# WiFi_TF_EMMC.net
KiCad netlist of a schematic drawn in Altium Designer
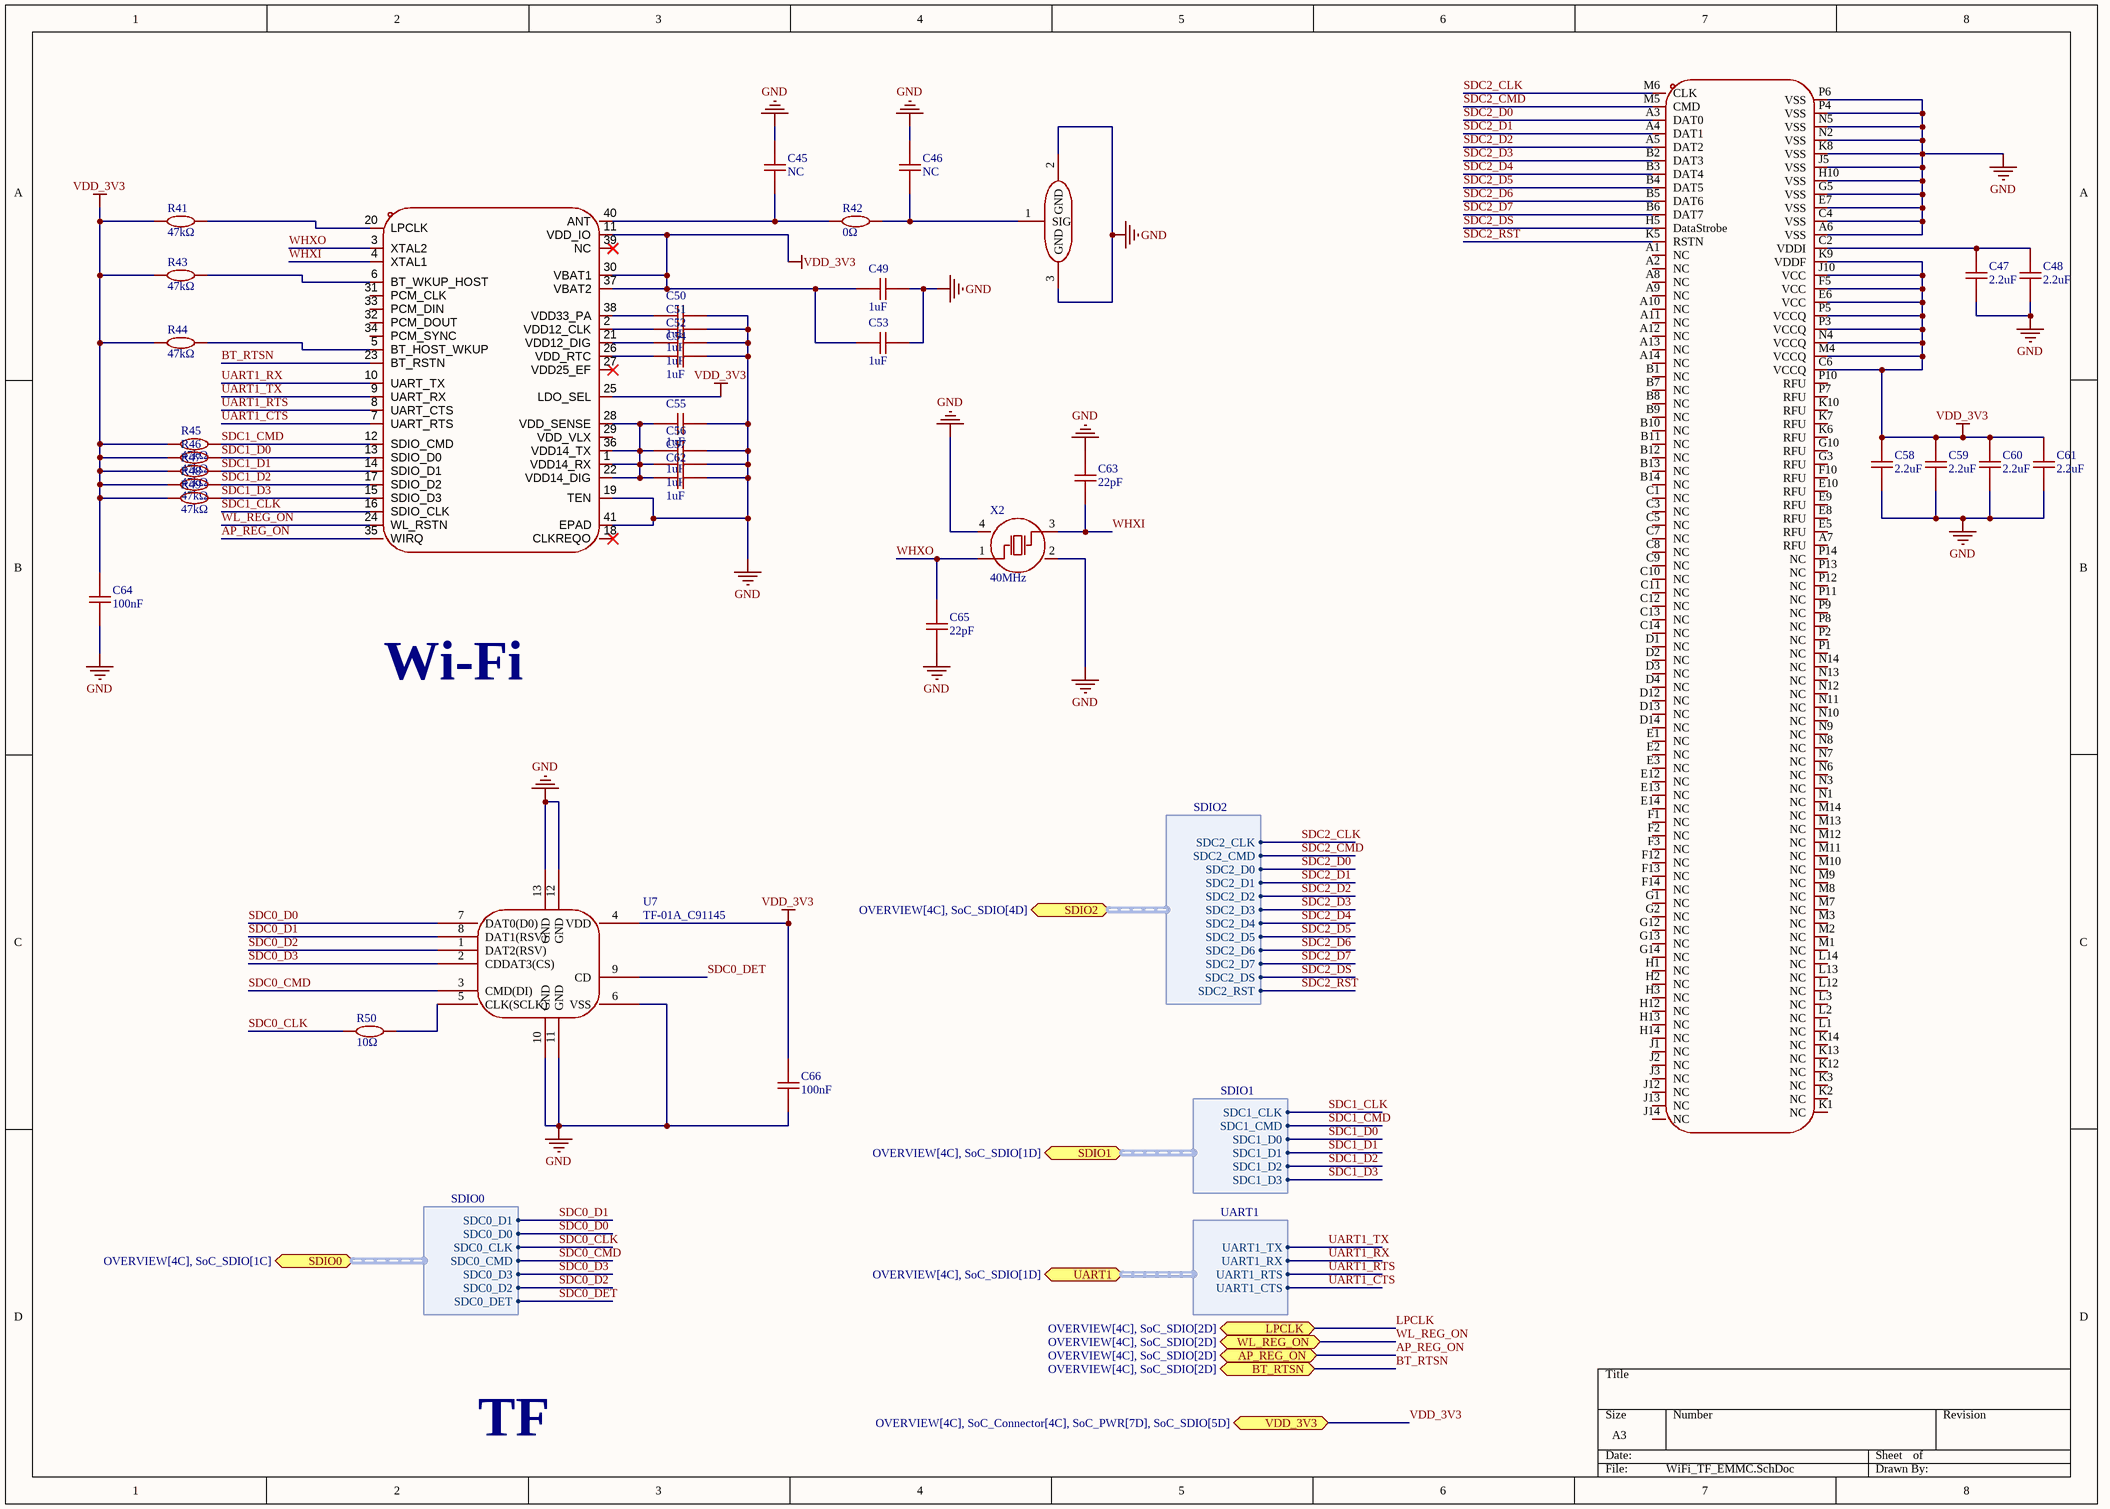
[diagram p0: WiFi_TF_EMMC.SchDoc]

(export (version "E")
  (design (tool "Eeschema 10.0.6"))
  (components
    (comp (ref "C45")
      (value "NC")
      (footprint "C0402")
      (description "50V 100nF X7R ±10% 0402 Ceramic Capacitors ROHS")
      (libsource (lib "RLC") (part "100nF"))
    )
    (comp (ref "C46")
      (value "NC")
      (footprint "C0402")
      (description "50V 100nF X7R ±10% 0402 Ceramic Capacitors ROHS")
      (libsource (lib "RLC") (part "100nF"))
    )
    (comp (ref "C47")
      (value "2.2uF")
      (footprint "C0402")
      (description "50V 2.2uF NP0 0402 Ceramic Capacitors ROHS")
      (libsource (lib "RLC") (part "2.2uF"))
    )
    (comp (ref "C48")
      (value "2.2uF")
      (footprint "C0402")
      (description "50V 2.2uF NP0 0402 Ceramic Capacitors ROHS")
      (libsource (lib "RLC") (part "2.2uF"))
    )
    (comp (ref "C49")
      (value "1uF")
      (footprint "C0402")
      (description "50V 1uF X5R ±10% 0402 Ceramic Capacitors ROHS")
      (libsource (lib "RLC") (part "1uF"))
    )
    (comp (ref "C50")
      (value "1uF")
      (footprint "C0402")
      (description "50V 1uF X5R ±10% 0402 Ceramic Capacitors ROHS")
      (libsource (lib "RLC") (part "1uF"))
    )
    (comp (ref "C51")
      (value "1uF")
      (footprint "C0402")
      (description "50V 1uF X5R ±10% 0402 Ceramic Capacitors ROHS")
      (libsource (lib "RLC") (part "1uF"))
    )
    (comp (ref "C52")
      (value "1uF")
      (footprint "C0402")
      (description "50V 1uF X5R ±10% 0402 Ceramic Capacitors ROHS")
      (libsource (lib "RLC") (part "1uF"))
    )
    (comp (ref "C53")
      (value "1uF")
      (footprint "C0402")
      (description "50V 1uF X5R ±10% 0402 Ceramic Capacitors ROHS")
      (libsource (lib "RLC") (part "1uF"))
    )
    (comp (ref "C54")
      (value "1uF")
      (footprint "C0402")
      (description "50V 1uF X5R ±10% 0402 Ceramic Capacitors ROHS")
      (libsource (lib "RLC") (part "1uF"))
    )
    (comp (ref "C55")
      (value "1uF")
      (footprint "C0402")
      (description "50V 1uF X5R ±10% 0402 Ceramic Capacitors ROHS")
      (libsource (lib "RLC") (part "1uF"))
    )
    (comp (ref "C56")
      (value "1uF")
      (footprint "C0402")
      (description "50V 1uF X5R ±10% 0402 Ceramic Capacitors ROHS")
      (libsource (lib "RLC") (part "1uF"))
    )
    (comp (ref "C57")
      (value "1uF")
      (footprint "C0402")
      (description "50V 1uF X5R ±10% 0402 Ceramic Capacitors ROHS")
      (libsource (lib "RLC") (part "1uF"))
    )
    (comp (ref "C58")
      (value "2.2uF")
      (footprint "C0402")
      (description "50V 2.2uF NP0 0402 Ceramic Capacitors ROHS")
      (libsource (lib "RLC") (part "2.2uF"))
    )
    (comp (ref "C59")
      (value "2.2uF")
      (footprint "C0402")
      (description "50V 2.2uF NP0 0402 Ceramic Capacitors ROHS")
      (libsource (lib "RLC") (part "2.2uF"))
    )
    (comp (ref "C60")
      (value "2.2uF")
      (footprint "C0402")
      (description "50V 2.2uF NP0 0402 Ceramic Capacitors ROHS")
      (libsource (lib "RLC") (part "2.2uF"))
    )
    (comp (ref "C61")
      (value "2.2uF")
      (footprint "C0402")
      (description "50V 2.2uF NP0 0402 Ceramic Capacitors ROHS")
      (libsource (lib "RLC") (part "2.2uF"))
    )
    (comp (ref "C62")
      (value "1uF")
      (footprint "C0402")
      (description "50V 1uF X5R ±10% 0402 Ceramic Capacitors ROHS")
      (libsource (lib "RLC") (part "1uF"))
    )
    (comp (ref "C63")
      (value "22pF")
      (footprint "C0402")
      (description "50V 22pF C0G ±5% 0402 Ceramic Capacitors ROHS")
      (libsource (lib "RLC") (part "22pF"))
    )
    (comp (ref "C64")
      (value "100nF")
      (footprint "C0402")
      (description "50V 100nF X7R ±10% 0402 Ceramic Capacitors ROHS")
      (libsource (lib "RLC") (part "100nF"))
    )
    (comp (ref "C65")
      (value "22pF")
      (footprint "C0402")
      (description "50V 22pF C0G ±5% 0402 Ceramic Capacitors ROHS")
      (libsource (lib "RLC") (part "22pF"))
    )
    (comp (ref "C66")
      (value "100nF")
      (footprint "C0402")
      (description "50V 100nF X7R ±10% 0402 Ceramic Capacitors ROHS")
      (libsource (lib "RLC") (part "100nF"))
    )
    (comp (ref "JP1")
      (value "6GHz")
      (footprint "RF-SMD_FRF05002-JSS103M")
      (fields (field (name "MANUFACTURER") "HRS(广濑)") (field (name "MANUFACTURER PART") "U.FL-R-SMT-1(80)"))
      (libsource (lib "Connector") (part "U.FL-R-SMT-1(80)_C88374"))
    )
    (comp (ref "R41")
      (value "47kΩ")
      (footprint "R0402")
      (description "62.5mW 47kΩ 50V ±100ppm/℃ Thick Film Resistor ±1% 0402 Chip Resistor - Surface Mount ROHS")
      (libsource (lib "RLC") (part "47kΩ"))
    )
    (comp (ref "R42")
      (value "0Ω")
      (footprint "R0402")
      (description "0Ω 62.5mW 50V Thick Film Resistor ±1% 0402 Chip Resistor - Surface Mount ROHS")
      (libsource (lib "RLC") (part "0Ω"))
    )
    (comp (ref "R43")
      (value "47kΩ")
      (footprint "R0402")
      (description "62.5mW 47kΩ 50V ±100ppm/℃ Thick Film Resistor ±1% 0402 Chip Resistor - Surface Mount ROHS")
      (libsource (lib "RLC") (part "47kΩ"))
    )
    (comp (ref "R44")
      (value "47kΩ")
      (footprint "R0402")
      (description "62.5mW 47kΩ 50V ±100ppm/℃ Thick Film Resistor ±1% 0402 Chip Resistor - Surface Mount ROHS")
      (libsource (lib "RLC") (part "47kΩ"))
    )
    (comp (ref "R45")
      (value "47kΩ")
      (footprint "R0402")
      (description "62.5mW 47kΩ 50V ±100ppm/℃ Thick Film Resistor ±1% 0402 Chip Resistor - Surface Mount ROHS")
      (libsource (lib "RLC") (part "47kΩ"))
    )
    (comp (ref "R46")
      (value "47kΩ")
      (footprint "R0402")
      (description "62.5mW 47kΩ 50V ±100ppm/℃ Thick Film Resistor ±1% 0402 Chip Resistor - Surface Mount ROHS")
      (libsource (lib "RLC") (part "47kΩ"))
    )
    (comp (ref "R47")
      (value "47kΩ")
      (footprint "R0402")
      (description "62.5mW 47kΩ 50V ±100ppm/℃ Thick Film Resistor ±1% 0402 Chip Resistor - Surface Mount ROHS")
      (libsource (lib "RLC") (part "47kΩ"))
    )
    (comp (ref "R48")
      (value "47kΩ")
      (footprint "R0402")
      (description "62.5mW 47kΩ 50V ±100ppm/℃ Thick Film Resistor ±1% 0402 Chip Resistor - Surface Mount ROHS")
      (libsource (lib "RLC") (part "47kΩ"))
    )
    (comp (ref "R49")
      (value "47kΩ")
      (footprint "R0402")
      (description "62.5mW 47kΩ 50V ±100ppm/℃ Thick Film Resistor ±1% 0402 Chip Resistor - Surface Mount ROHS")
      (libsource (lib "RLC") (part "47kΩ"))
    )
    (comp (ref "R50")
      (value "10Ω")
      (footprint "R0402")
      (description "10Ω 62.5mW 50V ±200ppm/℃ Thick Film Resistor ±1% 0402 Chip Resistor - Surface Mount ROHS")
      (libsource (lib "RLC") (part "10Ω"))
    )
    (comp (ref "U6")
      (value "XR829")
      (footprint "QFN-40_L5.0-W5.0-P0.40-BL-EP3.4")
      (description "2.4GHz WiFi and Bluetooth chips")
      (libsource (lib "IC") (part "XR829"))
    )
    (comp (ref "U7")
      (value "TF-01A_C91145")
      (footprint "TF-SMD_TF-01A")
      (description "Push-Push 1.85mm Connector and Ejector MicroSD Card (TF Card) SMD PC Card Sockets ROHS")
      (libsource (lib "IC") (part "TF-01A_C91145"))
    )
    (comp (ref "U8")
      (value "KLM8G1GETF-B041")
      (footprint "FBGA-153_L13.0-W11.5-P0.50_KLMAG1JETD-B041")
      (description "8GB 2.7V~3.6V eMMC 5.1 330/50 MB/s FBGA-153(11.5x13) Memory (ICs) ROHS")
      (fields (field (name "MANUFACTURER") "SAMSUNG(三星半导体)"))
      (libsource (lib "IC") (part "KLM8G1GETF-B041_1"))
    )
    (comp (ref "X2")
      (value "40MHz")
      (footprint "OSC-SMD_4P-L3.2-W2.5-BL_SIT8008BI")
      (description "Crystal Oscillator 15pF SMD3225-4P Crystals ROHS")
      (libsource (lib "OSC") (part "X322540MPB4SI"))
    )
  )
  (nets
    (net (code "5") (name "/AP_REG_ON") (class "Default")
      (node (ref "U6") (pin "35") (pinfunction "WIRQ_35") (pintype "passive"))
    )
    (net (code "6") (name "/BT_RTSN") (class "Default")
      (node (ref "U6") (pin "23") (pinfunction "BT_RSTN_23") (pintype "passive"))
    )
    (net (code "8") (name "/SDC0_CLK") (class "Default")
      (node (ref "R50") (pin "1") (pinfunction "1_1") (pintype "passive"))
    )
    (net (code "9") (name "/SDC0_CMD") (class "Default")
      (node (ref "U7") (pin "3") (pinfunction "CMD(DI)_3") (pintype "passive"))
    )
    (net (code "10") (name "/SDC0_D0") (class "Default")
      (node (ref "U7") (pin "7") (pinfunction "DAT0(D0)_7") (pintype "passive"))
    )
    (net (code "11") (name "/SDC0_D1") (class "Default")
      (node (ref "U7") (pin "8") (pinfunction "DAT1(RSV)_8") (pintype "passive"))
    )
    (net (code "12") (name "/SDC0_D2") (class "Default")
      (node (ref "U7") (pin "1") (pinfunction "DAT2(RSV)_1") (pintype "passive"))
    )
    (net (code "13") (name "/SDC0_D3") (class "Default")
      (node (ref "U7") (pin "2") (pinfunction "CDDAT3(CS)_2") (pintype "passive"))
    )
    (net (code "14") (name "/SDC0_DET") (class "Default")
      (node (ref "U7") (pin "9") (pinfunction "CD_9") (pintype "passive"))
    )
    (net (code "15") (name "/SDC1_CLK") (class "Default")
      (node (ref "U6") (pin "16") (pinfunction "SDIO_CLK_16") (pintype "passive"))
    )
    (net (code "16") (name "/SDC1_CMD") (class "Default")
      (node (ref "R45") (pin "2") (pinfunction "2_2") (pintype "passive"))
      (node (ref "U6") (pin "12") (pinfunction "SDIO_CMD_12") (pintype "passive"))
    )
    (net (code "17") (name "/SDC1_D0") (class "Default")
      (node (ref "R46") (pin "2") (pinfunction "2_2") (pintype "passive"))
      (node (ref "U6") (pin "13") (pinfunction "SDIO_D0_13") (pintype "passive"))
    )
    (net (code "18") (name "/SDC1_D1") (class "Default")
      (node (ref "R47") (pin "2") (pinfunction "2_2") (pintype "passive"))
      (node (ref "U6") (pin "14") (pinfunction "SDIO_D1_14") (pintype "passive"))
    )
    (net (code "19") (name "/SDC1_D2") (class "Default")
      (node (ref "R48") (pin "2") (pinfunction "2_2") (pintype "passive"))
      (node (ref "U6") (pin "17") (pinfunction "SDIO_D2_17") (pintype "passive"))
    )
    (net (code "20") (name "/SDC1_D3") (class "Default")
      (node (ref "R49") (pin "2") (pinfunction "2_2") (pintype "passive"))
      (node (ref "U6") (pin "15") (pinfunction "SDIO_D3_15") (pintype "passive"))
    )
    (net (code "21") (name "/SDC2_CLK") (class "Default")
      (node (ref "U8") (pin "M6") (pinfunction "CLK_M6") (pintype "passive"))
    )
    (net (code "22") (name "/SDC2_CMD") (class "Default")
      (node (ref "U8") (pin "M5") (pinfunction "CMD_M5") (pintype "passive"))
    )
    (net (code "23") (name "/SDC2_D0") (class "Default")
      (node (ref "U8") (pin "A3") (pinfunction "DAT0_A3") (pintype "passive"))
    )
    (net (code "24") (name "/SDC2_D1") (class "Default")
      (node (ref "U8") (pin "A4") (pinfunction "DAT1_A4") (pintype "passive"))
    )
    (net (code "25") (name "/SDC2_D2") (class "Default")
      (node (ref "U8") (pin "A5") (pinfunction "DAT2_A5") (pintype "passive"))
    )
    (net (code "26") (name "/SDC2_D3") (class "Default")
      (node (ref "U8") (pin "B2") (pinfunction "DAT3_B2") (pintype "passive"))
    )
    (net (code "27") (name "/SDC2_D4") (class "Default")
      (node (ref "U8") (pin "B3") (pinfunction "DAT4_B3") (pintype "passive"))
    )
    (net (code "28") (name "/SDC2_D5") (class "Default")
      (node (ref "U8") (pin "B4") (pinfunction "DAT5_B4") (pintype "passive"))
    )
    (net (code "29") (name "/SDC2_D6") (class "Default")
      (node (ref "U8") (pin "B5") (pinfunction "DAT6_B5") (pintype "passive"))
    )
    (net (code "30") (name "/SDC2_D7") (class "Default")
      (node (ref "U8") (pin "B6") (pinfunction "DAT7_B6") (pintype "passive"))
    )
    (net (code "31") (name "/SDC2_DS") (class "Default")
      (node (ref "U8") (pin "H5") (pinfunction "DataStrobe_H5") (pintype "passive"))
    )
    (net (code "32") (name "/SDC2_RST") (class "Default")
      (node (ref "U8") (pin "K5") (pinfunction "RSTN_K5") (pintype "passive"))
    )
    (net (code "33") (name "/UART1_CTS") (class "Default")
      (node (ref "U6") (pin "7") (pinfunction "UART_RTS_7") (pintype "passive"))
    )
    (net (code "34") (name "/UART1_RTS") (class "Default")
      (node (ref "U6") (pin "8") (pinfunction "UART_CTS_8") (pintype "passive"))
    )
    (net (code "35") (name "/UART1_RX") (class "Default")
      (node (ref "U6") (pin "10") (pinfunction "UART_TX_10") (pintype "passive"))
    )
    (net (code "36") (name "/UART1_TX") (class "Default")
      (node (ref "U6") (pin "9") (pinfunction "UART_RX_9") (pintype "passive"))
    )
    (net (code "37") (name "/WHXI") (class "Default")
      (node (ref "C63") (pin "1") (pinfunction "1_1") (pintype "passive"))
      (node (ref "U6") (pin "4") (pinfunction "XTAL1_4") (pintype "passive"))
      (node (ref "X2") (pin "3") (pinfunction "OSC2_3") (pintype "passive"))
    )
    (net (code "38") (name "/WHXO") (class "Default")
      (node (ref "C65") (pin "2") (pinfunction "2_2") (pintype "passive"))
      (node (ref "U6") (pin "3") (pinfunction "XTAL2_3") (pintype "passive"))
      (node (ref "X2") (pin "1") (pinfunction "OSC1_1") (pintype "passive"))
    )
    (net (code "39") (name "/WL_REG_ON") (class "Default")
      (node (ref "U6") (pin "24") (pinfunction "WL_RSTN_24") (pintype "passive"))
    )
    (net (code "44") (name "GND") (class "Default")
      (node (ref "C45") (pin "2") (pinfunction "2_2") (pintype "passive"))
      (node (ref "C46") (pin "2") (pinfunction "2_2") (pintype "passive"))
      (node (ref "C47") (pin "1") (pinfunction "1_1") (pintype "passive"))
      (node (ref "C48") (pin "1") (pinfunction "1_1") (pintype "passive"))
      (node (ref "C49") (pin "1") (pinfunction "1_1") (pintype "passive"))
      (node (ref "C50") (pin "1") (pinfunction "1_1") (pintype "passive"))
      (node (ref "C51") (pin "1") (pinfunction "1_1") (pintype "passive"))
      (node (ref "C52") (pin "1") (pinfunction "1_1") (pintype "passive"))
      (node (ref "C53") (pin "1") (pinfunction "1_1") (pintype "passive"))
      (node (ref "C54") (pin "1") (pinfunction "1_1") (pintype "passive"))
      (node (ref "C55") (pin "1") (pinfunction "1_1") (pintype "passive"))
      (node (ref "C56") (pin "1") (pinfunction "1_1") (pintype "passive"))
      (node (ref "C57") (pin "1") (pinfunction "1_1") (pintype "passive"))
      (node (ref "C58") (pin "1") (pinfunction "1_1") (pintype "passive"))
      (node (ref "C59") (pin "1") (pinfunction "1_1") (pintype "passive"))
      (node (ref "C60") (pin "1") (pinfunction "1_1") (pintype "passive"))
      (node (ref "C61") (pin "1") (pinfunction "1_1") (pintype "passive"))
      (node (ref "C62") (pin "1") (pinfunction "1_1") (pintype "passive"))
      (node (ref "C63") (pin "2") (pinfunction "2_2") (pintype "passive"))
      (node (ref "C64") (pin "1") (pinfunction "1_1") (pintype "passive"))
      (node (ref "C65") (pin "1") (pinfunction "1_1") (pintype "passive"))
      (node (ref "C66") (pin "1") (pinfunction "1_1") (pintype "passive"))
      (node (ref "JP1") (pin "2") (pinfunction "GND_2") (pintype "passive"))
      (node (ref "JP1") (pin "3") (pinfunction "GND_3") (pintype "passive"))
      (node (ref "U6") (pin "19") (pinfunction "TEN_19") (pintype "passive"))
      (node (ref "U6") (pin "41") (pinfunction "EPAD_41") (pintype "passive"))
      (node (ref "U7") (pin "10") (pinfunction "GND_10") (pintype "passive"))
      (node (ref "U7") (pin "11") (pinfunction "GND_11") (pintype "passive"))
      (node (ref "U7") (pin "12") (pinfunction "GND_12") (pintype "passive"))
      (node (ref "U7") (pin "13") (pinfunction "GND_13") (pintype "passive"))
      (node (ref "U7") (pin "6") (pinfunction "VSS_6") (pintype "passive"))
      (node (ref "U8") (pin "A6") (pinfunction "VSS_A6") (pintype "passive"))
      (node (ref "U8") (pin "C4") (pinfunction "VSS_C4") (pintype "passive"))
      (node (ref "U8") (pin "E7") (pinfunction "VSS_E7") (pintype "passive"))
      (node (ref "U8") (pin "G5") (pinfunction "VSS_G5") (pintype "passive"))
      (node (ref "U8") (pin "H10") (pinfunction "VSS_H10") (pintype "passive"))
      (node (ref "U8") (pin "J5") (pinfunction "VSS_J5") (pintype "passive"))
      (node (ref "U8") (pin "K8") (pinfunction "VSS_K8") (pintype "passive"))
      (node (ref "U8") (pin "N2") (pinfunction "VSS_N2") (pintype "passive"))
      (node (ref "U8") (pin "N5") (pinfunction "VSS_N5") (pintype "passive"))
      (node (ref "U8") (pin "P4") (pinfunction "VSS_P4") (pintype "passive"))
      (node (ref "U8") (pin "P6") (pinfunction "VSS_P6") (pintype "passive"))
      (node (ref "X2") (pin "2") (pinfunction "GND_2") (pintype "passive"))
      (node (ref "X2") (pin "4") (pinfunction "GND_4") (pintype "passive"))
    )
    (net (code "45") (name "Net-(JP1-SIG)") (class "Default")
      (node (ref "C46") (pin "1") (pinfunction "1_1") (pintype "passive"))
      (node (ref "JP1") (pin "1") (pinfunction "SIG_1") (pintype "passive"))
      (node (ref "R42") (pin "2") (pinfunction "2_2") (pintype "passive"))
    )
    (net (code "46") (name "Net-(U6-ANT)") (class "Default")
      (node (ref "C45") (pin "1") (pinfunction "1_1") (pintype "passive"))
      (node (ref "R42") (pin "1") (pinfunction "1_1") (pintype "passive"))
      (node (ref "U6") (pin "40") (pinfunction "ANT_40") (pintype "passive"))
    )
    (net (code "47") (name "Net-(U6-BT_HOST_WKUP)") (class "Default")
      (node (ref "R44") (pin "2") (pinfunction "2_2") (pintype "passive"))
      (node (ref "U6") (pin "5") (pinfunction "BT_HOST_WKUP_5") (pintype "passive"))
    )
    (net (code "48") (name "Net-(U6-BT_WKUP_HOST)") (class "Default")
      (node (ref "R43") (pin "2") (pinfunction "2_2") (pintype "passive"))
      (node (ref "U6") (pin "6") (pinfunction "BT_WKUP_HOST_6") (pintype "passive"))
    )
    (net (code "49") (name "Net-(U6-LPCLK)") (class "Default")
      (node (ref "R41") (pin "2") (pinfunction "2_2") (pintype "passive"))
      (node (ref "U6") (pin "20") (pinfunction "LPCLK_20") (pintype "passive"))
    )
    (net (code "50") (name "Net-(U6-VDD12_CLK)") (class "Default")
      (node (ref "C51") (pin "2") (pinfunction "2_2") (pintype "passive"))
      (node (ref "U6") (pin "2") (pinfunction "VDD12_CLK_2") (pintype "passive"))
    )
    (net (code "51") (name "Net-(U6-VDD12_DIG)") (class "Default")
      (node (ref "C52") (pin "2") (pinfunction "2_2") (pintype "passive"))
      (node (ref "U6") (pin "21") (pinfunction "VDD12_DIG_21") (pintype "passive"))
    )
    (net (code "52") (name "Net-(U6-VDD14_DIG)") (class "Default")
      (node (ref "C55") (pin "2") (pinfunction "2_2") (pintype "passive"))
      (node (ref "C56") (pin "2") (pinfunction "2_2") (pintype "passive"))
      (node (ref "C57") (pin "2") (pinfunction "2_2") (pintype "passive"))
      (node (ref "C62") (pin "2") (pinfunction "2_2") (pintype "passive"))
      (node (ref "U6") (pin "1") (pinfunction "VDD14_RX_1") (pintype "passive"))
      (node (ref "U6") (pin "22") (pinfunction "VDD14_DIG_22") (pintype "passive"))
      (node (ref "U6") (pin "28") (pinfunction "VDD_SENSE_28") (pintype "passive"))
      (node (ref "U6") (pin "36") (pinfunction "VDD14_TX_36") (pintype "passive"))
    )
    (net (code "53") (name "Net-(U6-VDD33_PA)") (class "Default")
      (node (ref "C50") (pin "2") (pinfunction "2_2") (pintype "passive"))
      (node (ref "U6") (pin "38") (pinfunction "VDD33_PA_38") (pintype "passive"))
    )
    (net (code "54") (name "Net-(U6-VDD_RTC)") (class "Default")
      (node (ref "C54") (pin "2") (pinfunction "2_2") (pintype "passive"))
      (node (ref "U6") (pin "26") (pinfunction "VDD_RTC_26") (pintype "passive"))
    )
    (net (code "55") (name "Net-(U7-CLK(SCLK))") (class "Default")
      (node (ref "R50") (pin "2") (pinfunction "2_2") (pintype "passive"))
      (node (ref "U7") (pin "5") (pinfunction "CLK(SCLK)_5") (pintype "passive"))
    )
    (net (code "56") (name "Net-(U8-VDDI)") (class "Default")
      (node (ref "C47") (pin "2") (pinfunction "2_2") (pintype "passive"))
      (node (ref "C48") (pin "2") (pinfunction "2_2") (pintype "passive"))
      (node (ref "U8") (pin "C2") (pinfunction "VDDI_C2") (pintype "passive"))
    )
    (net (code "57") (name "VDD_3V3") (class "Default")
      (node (ref "C49") (pin "2") (pinfunction "2_2") (pintype "passive"))
      (node (ref "C53") (pin "2") (pinfunction "2_2") (pintype "passive"))
      (node (ref "C58") (pin "2") (pinfunction "2_2") (pintype "passive"))
      (node (ref "C59") (pin "2") (pinfunction "2_2") (pintype "passive"))
      (node (ref "C60") (pin "2") (pinfunction "2_2") (pintype "passive"))
      (node (ref "C61") (pin "2") (pinfunction "2_2") (pintype "passive"))
      (node (ref "C64") (pin "2") (pinfunction "2_2") (pintype "passive"))
      (node (ref "C66") (pin "2") (pinfunction "2_2") (pintype "passive"))
      (node (ref "R41") (pin "1") (pinfunction "1_1") (pintype "passive"))
      (node (ref "R43") (pin "1") (pinfunction "1_1") (pintype "passive"))
      (node (ref "R44") (pin "1") (pinfunction "1_1") (pintype "passive"))
      (node (ref "R45") (pin "1") (pinfunction "1_1") (pintype "passive"))
      (node (ref "R46") (pin "1") (pinfunction "1_1") (pintype "passive"))
      (node (ref "R47") (pin "1") (pinfunction "1_1") (pintype "passive"))
      (node (ref "R48") (pin "1") (pinfunction "1_1") (pintype "passive"))
      (node (ref "R49") (pin "1") (pinfunction "1_1") (pintype "passive"))
      (node (ref "U6") (pin "11") (pinfunction "VDD_IO_11") (pintype "passive"))
      (node (ref "U6") (pin "25") (pinfunction "LDO_SEL_25") (pintype "passive"))
      (node (ref "U6") (pin "30") (pinfunction "VBAT1_30") (pintype "passive"))
      (node (ref "U6") (pin "37") (pinfunction "VBAT2_37") (pintype "passive"))
      (node (ref "U7") (pin "4") (pinfunction "VDD_4") (pintype "passive"))
      (node (ref "U8") (pin "C6") (pinfunction "VCCQ_C6") (pintype "passive"))
      (node (ref "U8") (pin "E6") (pinfunction "VCC_E6") (pintype "passive"))
      (node (ref "U8") (pin "F5") (pinfunction "VCC_F5") (pintype "passive"))
      (node (ref "U8") (pin "J10") (pinfunction "VCC_J10") (pintype "passive"))
      (node (ref "U8") (pin "K9") (pinfunction "VDDF_K9") (pintype "passive"))
      (node (ref "U8") (pin "M4") (pinfunction "VCCQ_M4") (pintype "passive"))
      (node (ref "U8") (pin "N4") (pinfunction "VCCQ_N4") (pintype "passive"))
      (node (ref "U8") (pin "P3") (pinfunction "VCCQ_P3") (pintype "passive"))
      (node (ref "U8") (pin "P5") (pinfunction "VCCQ_P5") (pintype "passive"))
    )
    (net (code "58") (name "unconnected-(U6-CLKREQO-Pad18)") (class "Default")
      (node (ref "U6") (pin "18") (pinfunction "CLKREQO_18") (pintype "passive+no_connect"))
    )
    (net (code "59") (name "unconnected-(U6-NC-Pad39)") (class "Default")
      (node (ref "U6") (pin "39") (pinfunction "NC_39") (pintype "passive+no_connect"))
    )
    (net (code "60") (name "unconnected-(U6-PCM_CLK-Pad31)") (class "Default")
      (node (ref "U6") (pin "31") (pinfunction "PCM_CLK_31") (pintype "passive"))
    )
    (net (code "61") (name "unconnected-(U6-PCM_DIN-Pad33)") (class "Default")
      (node (ref "U6") (pin "33") (pinfunction "PCM_DIN_33") (pintype "passive"))
    )
    (net (code "62") (name "unconnected-(U6-PCM_DOUT-Pad32)") (class "Default")
      (node (ref "U6") (pin "32") (pinfunction "PCM_DOUT_32") (pintype "passive"))
    )
    (net (code "63") (name "unconnected-(U6-PCM_SYNC-Pad34)") (class "Default")
      (node (ref "U6") (pin "34") (pinfunction "PCM_SYNC_34") (pintype "passive"))
    )
    (net (code "64") (name "unconnected-(U6-VDD25_EF-Pad27)") (class "Default")
      (node (ref "U6") (pin "27") (pinfunction "VDD25_EF_27") (pintype "passive+no_connect"))
    )
    (net (code "65") (name "unconnected-(U6-VDD_VLX-Pad29)") (class "Default")
      (node (ref "U6") (pin "29") (pinfunction "VDD_VLX_29") (pintype "passive"))
    )
    (net (code "66") (name "unconnected-(U8-NC-PadA1)") (class "Default")
      (node (ref "U8") (pin "A1") (pinfunction "NC_A1") (pintype "passive"))
    )
    (net (code "67") (name "unconnected-(U8-NC-PadA2)") (class "Default")
      (node (ref "U8") (pin "A2") (pinfunction "NC_A2") (pintype "passive"))
    )
    (net (code "68") (name "unconnected-(U8-NC-PadA8)") (class "Default")
      (node (ref "U8") (pin "A8") (pinfunction "NC_A8") (pintype "passive"))
    )
    (net (code "69") (name "unconnected-(U8-NC-PadA9)") (class "Default")
      (node (ref "U8") (pin "A9") (pinfunction "NC_A9") (pintype "passive"))
    )
    (net (code "70") (name "unconnected-(U8-NC-PadA10)") (class "Default")
      (node (ref "U8") (pin "A10") (pinfunction "NC_A10") (pintype "passive"))
    )
    (net (code "71") (name "unconnected-(U8-NC-PadA11)") (class "Default")
      (node (ref "U8") (pin "A11") (pinfunction "NC_A11") (pintype "passive"))
    )
    (net (code "72") (name "unconnected-(U8-NC-PadA12)") (class "Default")
      (node (ref "U8") (pin "A12") (pinfunction "NC_A12") (pintype "passive"))
    )
    (net (code "73") (name "unconnected-(U8-NC-PadA13)") (class "Default")
      (node (ref "U8") (pin "A13") (pinfunction "NC_A13") (pintype "passive"))
    )
    (net (code "74") (name "unconnected-(U8-NC-PadA14)") (class "Default")
      (node (ref "U8") (pin "A14") (pinfunction "NC_A14") (pintype "passive"))
    )
    (net (code "75") (name "unconnected-(U8-NC-PadB1)") (class "Default")
      (node (ref "U8") (pin "B1") (pinfunction "NC_B1") (pintype "passive"))
    )
    (net (code "76") (name "unconnected-(U8-NC-PadB7)") (class "Default")
      (node (ref "U8") (pin "B7") (pinfunction "NC_B7") (pintype "passive"))
    )
    (net (code "77") (name "unconnected-(U8-NC-PadB8)") (class "Default")
      (node (ref "U8") (pin "B8") (pinfunction "NC_B8") (pintype "passive"))
    )
    (net (code "78") (name "unconnected-(U8-NC-PadB9)") (class "Default")
      (node (ref "U8") (pin "B9") (pinfunction "NC_B9") (pintype "passive"))
    )
    (net (code "79") (name "unconnected-(U8-NC-PadB10)") (class "Default")
      (node (ref "U8") (pin "B10") (pinfunction "NC_B10") (pintype "passive"))
    )
    (net (code "80") (name "unconnected-(U8-NC-PadB11)") (class "Default")
      (node (ref "U8") (pin "B11") (pinfunction "NC_B11") (pintype "passive"))
    )
    (net (code "81") (name "unconnected-(U8-NC-PadB12)") (class "Default")
      (node (ref "U8") (pin "B12") (pinfunction "NC_B12") (pintype "passive"))
    )
    (net (code "82") (name "unconnected-(U8-NC-PadB13)") (class "Default")
      (node (ref "U8") (pin "B13") (pinfunction "NC_B13") (pintype "passive"))
    )
    (net (code "83") (name "unconnected-(U8-NC-PadB14)") (class "Default")
      (node (ref "U8") (pin "B14") (pinfunction "NC_B14") (pintype "passive"))
    )
    (net (code "84") (name "unconnected-(U8-NC-PadC1)") (class "Default")
      (node (ref "U8") (pin "C1") (pinfunction "NC_C1") (pintype "passive"))
    )
    (net (code "85") (name "unconnected-(U8-NC-PadC3)") (class "Default")
      (node (ref "U8") (pin "C3") (pinfunction "NC_C3") (pintype "passive"))
    )
    (net (code "86") (name "unconnected-(U8-NC-PadC5)") (class "Default")
      (node (ref "U8") (pin "C5") (pinfunction "NC_C5") (pintype "passive"))
    )
    (net (code "87") (name "unconnected-(U8-NC-PadC7)") (class "Default")
      (node (ref "U8") (pin "C7") (pinfunction "NC_C7") (pintype "passive"))
    )
    (net (code "88") (name "unconnected-(U8-NC-PadC8)") (class "Default")
      (node (ref "U8") (pin "C8") (pinfunction "NC_C8") (pintype "passive"))
    )
    (net (code "89") (name "unconnected-(U8-NC-PadC9)") (class "Default")
      (node (ref "U8") (pin "C9") (pinfunction "NC_C9") (pintype "passive"))
    )
    (net (code "90") (name "unconnected-(U8-NC-PadC10)") (class "Default")
      (node (ref "U8") (pin "C10") (pinfunction "NC_C10") (pintype "passive"))
    )
    (net (code "91") (name "unconnected-(U8-NC-PadC11)") (class "Default")
      (node (ref "U8") (pin "C11") (pinfunction "NC_C11") (pintype "passive"))
    )
    (net (code "92") (name "unconnected-(U8-NC-PadC12)") (class "Default")
      (node (ref "U8") (pin "C12") (pinfunction "NC_C12") (pintype "passive"))
    )
    (net (code "93") (name "unconnected-(U8-NC-PadC13)") (class "Default")
      (node (ref "U8") (pin "C13") (pinfunction "NC_C13") (pintype "passive"))
    )
    (net (code "94") (name "unconnected-(U8-NC-PadC14)") (class "Default")
      (node (ref "U8") (pin "C14") (pinfunction "NC_C14") (pintype "passive"))
    )
    (net (code "95") (name "unconnected-(U8-NC-PadD1)") (class "Default")
      (node (ref "U8") (pin "D1") (pinfunction "NC_D1") (pintype "passive"))
    )
    (net (code "96") (name "unconnected-(U8-NC-PadD2)") (class "Default")
      (node (ref "U8") (pin "D2") (pinfunction "NC_D2") (pintype "passive"))
    )
    (net (code "97") (name "unconnected-(U8-NC-PadD3)") (class "Default")
      (node (ref "U8") (pin "D3") (pinfunction "NC_D3") (pintype "passive"))
    )
    (net (code "98") (name "unconnected-(U8-NC-PadD4)") (class "Default")
      (node (ref "U8") (pin "D4") (pinfunction "NC_D4") (pintype "passive"))
    )
    (net (code "99") (name "unconnected-(U8-NC-PadD12)") (class "Default")
      (node (ref "U8") (pin "D12") (pinfunction "NC_D12") (pintype "passive"))
    )
    (net (code "100") (name "unconnected-(U8-NC-PadD13)") (class "Default")
      (node (ref "U8") (pin "D13") (pinfunction "NC_D13") (pintype "passive"))
    )
    (net (code "101") (name "unconnected-(U8-NC-PadD14)") (class "Default")
      (node (ref "U8") (pin "D14") (pinfunction "NC_D14") (pintype "passive"))
    )
    (net (code "102") (name "unconnected-(U8-NC-PadE1)") (class "Default")
      (node (ref "U8") (pin "E1") (pinfunction "NC_E1") (pintype "passive"))
    )
    (net (code "103") (name "unconnected-(U8-NC-PadE2)") (class "Default")
      (node (ref "U8") (pin "E2") (pinfunction "NC_E2") (pintype "passive"))
    )
    (net (code "104") (name "unconnected-(U8-NC-PadE3)") (class "Default")
      (node (ref "U8") (pin "E3") (pinfunction "NC_E3") (pintype "passive"))
    )
    (net (code "105") (name "unconnected-(U8-NC-PadE12)") (class "Default")
      (node (ref "U8") (pin "E12") (pinfunction "NC_E12") (pintype "passive"))
    )
    (net (code "106") (name "unconnected-(U8-NC-PadE13)") (class "Default")
      (node (ref "U8") (pin "E13") (pinfunction "NC_E13") (pintype "passive"))
    )
    (net (code "107") (name "unconnected-(U8-NC-PadE14)") (class "Default")
      (node (ref "U8") (pin "E14") (pinfunction "NC_E14") (pintype "passive"))
    )
    (net (code "108") (name "unconnected-(U8-NC-PadF1)") (class "Default")
      (node (ref "U8") (pin "F1") (pinfunction "NC_F1") (pintype "passive"))
    )
    (net (code "109") (name "unconnected-(U8-NC-PadF2)") (class "Default")
      (node (ref "U8") (pin "F2") (pinfunction "NC_F2") (pintype "passive"))
    )
    (net (code "110") (name "unconnected-(U8-NC-PadF3)") (class "Default")
      (node (ref "U8") (pin "F3") (pinfunction "NC_F3") (pintype "passive"))
    )
    (net (code "111") (name "unconnected-(U8-NC-PadF12)") (class "Default")
      (node (ref "U8") (pin "F12") (pinfunction "NC_F12") (pintype "passive"))
    )
    (net (code "112") (name "unconnected-(U8-NC-PadF13)") (class "Default")
      (node (ref "U8") (pin "F13") (pinfunction "NC_F13") (pintype "passive"))
    )
    (net (code "113") (name "unconnected-(U8-NC-PadF14)") (class "Default")
      (node (ref "U8") (pin "F14") (pinfunction "NC_F14") (pintype "passive"))
    )
    (net (code "114") (name "unconnected-(U8-NC-PadG1)") (class "Default")
      (node (ref "U8") (pin "G1") (pinfunction "NC_G1") (pintype "passive"))
    )
    (net (code "115") (name "unconnected-(U8-NC-PadG2)") (class "Default")
      (node (ref "U8") (pin "G2") (pinfunction "NC_G2") (pintype "passive"))
    )
    (net (code "116") (name "unconnected-(U8-NC-PadG12)") (class "Default")
      (node (ref "U8") (pin "G12") (pinfunction "NC_G12") (pintype "passive"))
    )
    (net (code "117") (name "unconnected-(U8-NC-PadG13)") (class "Default")
      (node (ref "U8") (pin "G13") (pinfunction "NC_G13") (pintype "passive"))
    )
    (net (code "118") (name "unconnected-(U8-NC-PadG14)") (class "Default")
      (node (ref "U8") (pin "G14") (pinfunction "NC_G14") (pintype "passive"))
    )
    (net (code "119") (name "unconnected-(U8-NC-PadH1)") (class "Default")
      (node (ref "U8") (pin "H1") (pinfunction "NC_H1") (pintype "passive"))
    )
    (net (code "120") (name "unconnected-(U8-NC-PadH2)") (class "Default")
      (node (ref "U8") (pin "H2") (pinfunction "NC_H2") (pintype "passive"))
    )
    (net (code "121") (name "unconnected-(U8-NC-PadH3)") (class "Default")
      (node (ref "U8") (pin "H3") (pinfunction "NC_H3") (pintype "passive"))
    )
    (net (code "122") (name "unconnected-(U8-NC-PadH12)") (class "Default")
      (node (ref "U8") (pin "H12") (pinfunction "NC_H12") (pintype "passive"))
    )
    (net (code "123") (name "unconnected-(U8-NC-PadH13)") (class "Default")
      (node (ref "U8") (pin "H13") (pinfunction "NC_H13") (pintype "passive"))
    )
    (net (code "124") (name "unconnected-(U8-NC-PadH14)") (class "Default")
      (node (ref "U8") (pin "H14") (pinfunction "NC_H14") (pintype "passive"))
    )
    (net (code "125") (name "unconnected-(U8-NC-PadJ1)") (class "Default")
      (node (ref "U8") (pin "J1") (pinfunction "NC_J1") (pintype "passive"))
    )
    (net (code "126") (name "unconnected-(U8-NC-PadJ2)") (class "Default")
      (node (ref "U8") (pin "J2") (pinfunction "NC_J2") (pintype "passive"))
    )
    (net (code "127") (name "unconnected-(U8-NC-PadJ3)") (class "Default")
      (node (ref "U8") (pin "J3") (pinfunction "NC_J3") (pintype "passive"))
    )
    (net (code "128") (name "unconnected-(U8-NC-PadJ12)") (class "Default")
      (node (ref "U8") (pin "J12") (pinfunction "NC_J12") (pintype "passive"))
    )
    (net (code "129") (name "unconnected-(U8-NC-PadJ13)") (class "Default")
      (node (ref "U8") (pin "J13") (pinfunction "NC_J13") (pintype "passive"))
    )
    (net (code "130") (name "unconnected-(U8-NC-PadJ14)") (class "Default")
      (node (ref "U8") (pin "J14") (pinfunction "NC_J14") (pintype "passive"))
    )
    (net (code "131") (name "unconnected-(U8-NC-PadK1)") (class "Default")
      (node (ref "U8") (pin "K1") (pinfunction "NC_K1") (pintype "passive"))
    )
    (net (code "132") (name "unconnected-(U8-NC-PadK2)") (class "Default")
      (node (ref "U8") (pin "K2") (pinfunction "NC_K2") (pintype "passive"))
    )
    (net (code "133") (name "unconnected-(U8-NC-PadK3)") (class "Default")
      (node (ref "U8") (pin "K3") (pinfunction "NC_K3") (pintype "passive"))
    )
    (net (code "134") (name "unconnected-(U8-NC-PadK12)") (class "Default")
      (node (ref "U8") (pin "K12") (pinfunction "NC_K12") (pintype "passive"))
    )
    (net (code "135") (name "unconnected-(U8-NC-PadK13)") (class "Default")
      (node (ref "U8") (pin "K13") (pinfunction "NC_K13") (pintype "passive"))
    )
    (net (code "136") (name "unconnected-(U8-NC-PadK14)") (class "Default")
      (node (ref "U8") (pin "K14") (pinfunction "NC_K14") (pintype "passive"))
    )
    (net (code "137") (name "unconnected-(U8-NC-PadL1)") (class "Default")
      (node (ref "U8") (pin "L1") (pinfunction "NC_L1") (pintype "passive"))
    )
    (net (code "138") (name "unconnected-(U8-NC-PadL2)") (class "Default")
      (node (ref "U8") (pin "L2") (pinfunction "NC_L2") (pintype "passive"))
    )
    (net (code "139") (name "unconnected-(U8-NC-PadL3)") (class "Default")
      (node (ref "U8") (pin "L3") (pinfunction "NC_L3") (pintype "passive"))
    )
    (net (code "140") (name "unconnected-(U8-NC-PadL12)") (class "Default")
      (node (ref "U8") (pin "L12") (pinfunction "NC_L12") (pintype "passive"))
    )
    (net (code "141") (name "unconnected-(U8-NC-PadL13)") (class "Default")
      (node (ref "U8") (pin "L13") (pinfunction "NC_L13") (pintype "passive"))
    )
    (net (code "142") (name "unconnected-(U8-NC-PadL14)") (class "Default")
      (node (ref "U8") (pin "L14") (pinfunction "NC_L14") (pintype "passive"))
    )
    (net (code "143") (name "unconnected-(U8-NC-PadM1)") (class "Default")
      (node (ref "U8") (pin "M1") (pinfunction "NC_M1") (pintype "passive"))
    )
    (net (code "144") (name "unconnected-(U8-NC-PadM2)") (class "Default")
      (node (ref "U8") (pin "M2") (pinfunction "NC_M2") (pintype "passive"))
    )
    (net (code "145") (name "unconnected-(U8-NC-PadM3)") (class "Default")
      (node (ref "U8") (pin "M3") (pinfunction "NC_M3") (pintype "passive"))
    )
    (net (code "146") (name "unconnected-(U8-NC-PadM7)") (class "Default")
      (node (ref "U8") (pin "M7") (pinfunction "NC_M7") (pintype "passive"))
    )
    (net (code "147") (name "unconnected-(U8-NC-PadM8)") (class "Default")
      (node (ref "U8") (pin "M8") (pinfunction "NC_M8") (pintype "passive"))
    )
    (net (code "148") (name "unconnected-(U8-NC-PadM9)") (class "Default")
      (node (ref "U8") (pin "M9") (pinfunction "NC_M9") (pintype "passive"))
    )
    (net (code "149") (name "unconnected-(U8-NC-PadM10)") (class "Default")
      (node (ref "U8") (pin "M10") (pinfunction "NC_M10") (pintype "passive"))
    )
    (net (code "150") (name "unconnected-(U8-NC-PadM11)") (class "Default")
      (node (ref "U8") (pin "M11") (pinfunction "NC_M11") (pintype "passive"))
    )
    (net (code "151") (name "unconnected-(U8-NC-PadM12)") (class "Default")
      (node (ref "U8") (pin "M12") (pinfunction "NC_M12") (pintype "passive"))
    )
    (net (code "152") (name "unconnected-(U8-NC-PadM13)") (class "Default")
      (node (ref "U8") (pin "M13") (pinfunction "NC_M13") (pintype "passive"))
    )
    (net (code "153") (name "unconnected-(U8-NC-PadM14)") (class "Default")
      (node (ref "U8") (pin "M14") (pinfunction "NC_M14") (pintype "passive"))
    )
    (net (code "154") (name "unconnected-(U8-NC-PadN1)") (class "Default")
      (node (ref "U8") (pin "N1") (pinfunction "NC_N1") (pintype "passive"))
    )
    (net (code "155") (name "unconnected-(U8-NC-PadN3)") (class "Default")
      (node (ref "U8") (pin "N3") (pinfunction "NC_N3") (pintype "passive"))
    )
    (net (code "156") (name "unconnected-(U8-NC-PadN6)") (class "Default")
      (node (ref "U8") (pin "N6") (pinfunction "NC_N6") (pintype "passive"))
    )
    (net (code "157") (name "unconnected-(U8-NC-PadN7)") (class "Default")
      (node (ref "U8") (pin "N7") (pinfunction "NC_N7") (pintype "passive"))
    )
    (net (code "158") (name "unconnected-(U8-NC-PadN8)") (class "Default")
      (node (ref "U8") (pin "N8") (pinfunction "NC_N8") (pintype "passive"))
    )
    (net (code "159") (name "unconnected-(U8-NC-PadN9)") (class "Default")
      (node (ref "U8") (pin "N9") (pinfunction "NC_N9") (pintype "passive"))
    )
    (net (code "160") (name "unconnected-(U8-NC-PadN10)") (class "Default")
      (node (ref "U8") (pin "N10") (pinfunction "NC_N10") (pintype "passive"))
    )
    (net (code "161") (name "unconnected-(U8-NC-PadN11)") (class "Default")
      (node (ref "U8") (pin "N11") (pinfunction "NC_N11") (pintype "passive"))
    )
    (net (code "162") (name "unconnected-(U8-NC-PadN12)") (class "Default")
      (node (ref "U8") (pin "N12") (pinfunction "NC_N12") (pintype "passive"))
    )
    (net (code "163") (name "unconnected-(U8-NC-PadN13)") (class "Default")
      (node (ref "U8") (pin "N13") (pinfunction "NC_N13") (pintype "passive"))
    )
    (net (code "164") (name "unconnected-(U8-NC-PadN14)") (class "Default")
      (node (ref "U8") (pin "N14") (pinfunction "NC_N14") (pintype "passive"))
    )
    (net (code "165") (name "unconnected-(U8-NC-PadP1)") (class "Default")
      (node (ref "U8") (pin "P1") (pinfunction "NC_P1") (pintype "passive"))
    )
    (net (code "166") (name "unconnected-(U8-NC-PadP2)") (class "Default")
      (node (ref "U8") (pin "P2") (pinfunction "NC_P2") (pintype "passive"))
    )
    (net (code "167") (name "unconnected-(U8-NC-PadP8)") (class "Default")
      (node (ref "U8") (pin "P8") (pinfunction "NC_P8") (pintype "passive"))
    )
    (net (code "168") (name "unconnected-(U8-NC-PadP9)") (class "Default")
      (node (ref "U8") (pin "P9") (pinfunction "NC_P9") (pintype "passive"))
    )
    (net (code "169") (name "unconnected-(U8-NC-PadP11)") (class "Default")
      (node (ref "U8") (pin "P11") (pinfunction "NC_P11") (pintype "passive"))
    )
    (net (code "170") (name "unconnected-(U8-NC-PadP12)") (class "Default")
      (node (ref "U8") (pin "P12") (pinfunction "NC_P12") (pintype "passive"))
    )
    (net (code "171") (name "unconnected-(U8-NC-PadP13)") (class "Default")
      (node (ref "U8") (pin "P13") (pinfunction "NC_P13") (pintype "passive"))
    )
    (net (code "172") (name "unconnected-(U8-NC-PadP14)") (class "Default")
      (node (ref "U8") (pin "P14") (pinfunction "NC_P14") (pintype "passive"))
    )
    (net (code "173") (name "unconnected-(U8-RFU-PadA7)") (class "Default")
      (node (ref "U8") (pin "A7") (pinfunction "RFU_A7") (pintype "passive"))
    )
    (net (code "174") (name "unconnected-(U8-RFU-PadE5)") (class "Default")
      (node (ref "U8") (pin "E5") (pinfunction "RFU_E5") (pintype "passive"))
    )
    (net (code "175") (name "unconnected-(U8-RFU-PadE8)") (class "Default")
      (node (ref "U8") (pin "E8") (pinfunction "RFU_E8") (pintype "passive"))
    )
    (net (code "176") (name "unconnected-(U8-RFU-PadE9)") (class "Default")
      (node (ref "U8") (pin "E9") (pinfunction "RFU_E9") (pintype "passive"))
    )
    (net (code "177") (name "unconnected-(U8-RFU-PadE10)") (class "Default")
      (node (ref "U8") (pin "E10") (pinfunction "RFU_E10") (pintype "passive"))
    )
    (net (code "178") (name "unconnected-(U8-RFU-PadF10)") (class "Default")
      (node (ref "U8") (pin "F10") (pinfunction "RFU_F10") (pintype "passive"))
    )
    (net (code "179") (name "unconnected-(U8-RFU-PadG3)") (class "Default")
      (node (ref "U8") (pin "G3") (pinfunction "RFU_G3") (pintype "passive"))
    )
    (net (code "180") (name "unconnected-(U8-RFU-PadG10)") (class "Default")
      (node (ref "U8") (pin "G10") (pinfunction "RFU_G10") (pintype "passive"))
    )
    (net (code "181") (name "unconnected-(U8-RFU-PadK6)") (class "Default")
      (node (ref "U8") (pin "K6") (pinfunction "RFU_K6") (pintype "passive"))
    )
    (net (code "182") (name "unconnected-(U8-RFU-PadK7)") (class "Default")
      (node (ref "U8") (pin "K7") (pinfunction "RFU_K7") (pintype "passive"))
    )
    (net (code "183") (name "unconnected-(U8-RFU-PadK10)") (class "Default")
      (node (ref "U8") (pin "K10") (pinfunction "RFU_K10") (pintype "passive"))
    )
    (net (code "184") (name "unconnected-(U8-RFU-PadP7)") (class "Default")
      (node (ref "U8") (pin "P7") (pinfunction "RFU_P7") (pintype "passive"))
    )
    (net (code "185") (name "unconnected-(U8-RFU-PadP10)") (class "Default")
      (node (ref "U8") (pin "P10") (pinfunction "RFU_P10") (pintype "passive"))
    )
  )
)
